# miliohmmeter.net
KiCad netlist of a schematic drawn in EAGLE
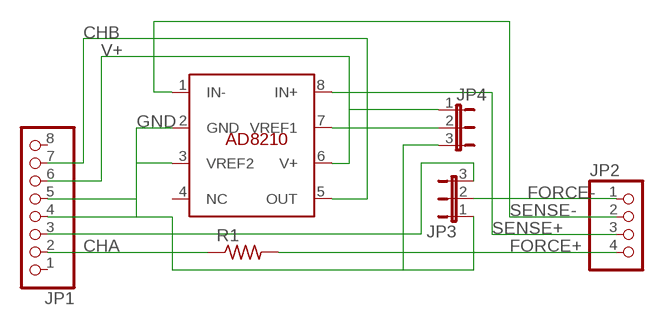
[diagram p0: schematic, sheet 1]

(export (version "E")
  (design (tool "Eeschema 10.0.6"))
  (components
    (comp (ref "JP1")
      (value "PINHD-1X8")
      (footprint "eagle-import:1X08")
      (libsource (lib "eagle-import") (part "PINHD-1X8"))
    )
    (comp (ref "JP2")
      (value "PINHD-1X4")
      (footprint "eagle-import:1X04")
      (libsource (lib "eagle-import") (part "PINHD-1X4"))
    )
    (comp (ref "JP3")
      (value "JP2E")
      (footprint "eagle-import:JP2")
      (libsource (lib "eagle-import") (part "JP2E"))
    )
    (comp (ref "JP4")
      (value "JP2E")
      (footprint "eagle-import:JP2")
      (libsource (lib "eagle-import") (part "JP2E"))
    )
    (comp (ref "R1")
      (value "R-US_0207/10")
      (footprint "eagle-import:0207_10")
      (libsource (lib "eagle-import") (part "R-US_0207/10"))
    )
    (comp (ref "U1")
      (value "AD8210")
      (footprint "eagle-import:SO8")
      (libsource (lib "eagle-import") (part "AD8210"))
    )
  )
  (nets
    (net (code "1") (name "/CHA") (class "Default")
      (node (ref "JP1") (pin "2") (pinfunction "2_2") (pintype "passive"))
      (node (ref "R1") (pin "1") (pinfunction "1_1") (pintype "passive"))
    )
    (net (code "2") (name "/CHB") (class "Default")
      (node (ref "JP1") (pin "7") (pinfunction "7_7") (pintype "passive"))
      (node (ref "U1") (pin "5") (pinfunction "OUT_5") (pintype "bidirectional"))
    )
    (net (code "3") (name "/FORCE+") (class "Default")
      (node (ref "JP2") (pin "4") (pinfunction "4_4") (pintype "passive"))
      (node (ref "R1") (pin "2") (pinfunction "2_2") (pintype "passive"))
    )
    (net (code "4") (name "/FORCE-") (class "Default")
      (node (ref "JP2") (pin "1") (pinfunction "1_1") (pintype "passive"))
      (node (ref "JP3") (pin "2") (pinfunction "2_2") (pintype "passive"))
    )
    (net (code "5") (name "/GND") (class "Default")
      (node (ref "JP1") (pin "4") (pinfunction "4_4") (pintype "passive"))
      (node (ref "JP1") (pin "5") (pinfunction "5_5") (pintype "passive"))
      (node (ref "JP3") (pin "1") (pinfunction "1_1") (pintype "passive"))
      (node (ref "JP4") (pin "3") (pinfunction "3_3") (pintype "passive"))
      (node (ref "U1") (pin "2") (pinfunction "GND_2") (pintype "bidirectional"))
      (node (ref "U1") (pin "3") (pinfunction "VREF2_3") (pintype "bidirectional"))
    )
    (net (code "6") (name "/SENSE+") (class "Default")
      (node (ref "JP2") (pin "3") (pinfunction "3_3") (pintype "passive"))
      (node (ref "U1") (pin "8") (pinfunction "IN+_8") (pintype "bidirectional"))
    )
    (net (code "7") (name "/SENSE-") (class "Default")
      (node (ref "JP2") (pin "2") (pinfunction "2_2") (pintype "passive"))
      (node (ref "U1") (pin "1") (pinfunction "IN-_1") (pintype "bidirectional"))
    )
    (net (code "8") (name "/V+") (class "Default")
      (node (ref "JP1") (pin "6") (pinfunction "6_6") (pintype "passive"))
      (node (ref "JP4") (pin "1") (pinfunction "1_1") (pintype "passive"))
      (node (ref "U1") (pin "6") (pinfunction "V+_6") (pintype "bidirectional"))
    )
    (net (code "9") (name "Net-(JP1-Pad3)") (class "Default")
      (node (ref "JP1") (pin "3") (pinfunction "3_3") (pintype "passive"))
      (node (ref "JP3") (pin "3") (pinfunction "3_3") (pintype "passive"))
    )
    (net (code "10") (name "Net-(U1-VREF1)") (class "Default")
      (node (ref "JP4") (pin "2") (pinfunction "2_2") (pintype "passive"))
      (node (ref "U1") (pin "7") (pinfunction "VREF1_7") (pintype "bidirectional"))
    )
    (net (code "11") (name "unconnected-(JP1-Pad1)") (class "Default")
      (node (ref "JP1") (pin "1") (pinfunction "1_1") (pintype "passive"))
    )
    (net (code "12") (name "unconnected-(JP1-Pad8)") (class "Default")
      (node (ref "JP1") (pin "8") (pinfunction "8_8") (pintype "passive"))
    )
    (net (code "13") (name "unconnected-(U1-NC-Pad4)") (class "Default")
      (node (ref "U1") (pin "4") (pinfunction "NC_4") (pintype "bidirectional"))
    )
  )
)
